# multiplexer-ic.net
KiCad netlist of a schematic drawn in Altium Designer
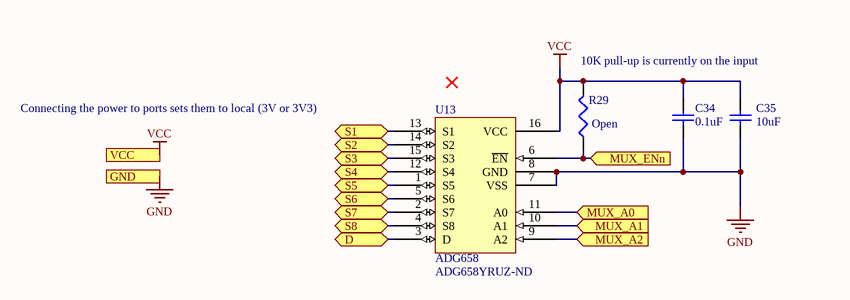
[diagram p0: multiplexer-ic.SchDoc]

(export (version "E")
  (design (tool "Eeschema 10.0.6"))
  (components
    (comp (ref "C34")
      (value "0.1uF")
      (footprint "0402")
      (description "Capacitor (Semiconductor SIM Model)")
      (fields (field (name "PUBLISHER") "Altium Limited"))
      (libsource (lib "Miscellaneous Devices") (part "Cap Semi"))
    )
    (comp (ref "C35")
      (value "10uF")
      (footprint "1608[0603]")
      (description "Capacitor (Semiconductor SIM Model)")
      (fields (field (name "PUBLISHER") "Altium Limited"))
      (libsource (lib "Miscellaneous Devices") (part "Cap Semi"))
    )
    (comp (ref "R29")
      (value "Open")
      (footprint "0402")
      (description "Resistor")
      (fields (field (name "Comment") "Optional 10K") (field (name "PUBLISHER") "Altium Limited"))
      (libsource (lib "Miscellaneous Devices") (part "Res3"))
    )
    (comp (ref "U13")
      (value "ADG658")
      (footprint "SSOP16_N")
      (description "Eight channel analog multiplexer.")
      (fields (field (name "SUPPLIER PART NUMBER 1") "ADG658YRUZ-ND"))
      (libsource (lib "PAY") (part "ADG658"))
    )
  )
  (nets
    (net (code "1") (name "/D") (class "Default")
      (node (ref "U13") (pin "3") (pinfunction "D_3") (pintype "bidirectional"))
    )
    (net (code "2") (name "/MUX_A0") (class "Default")
      (node (ref "U13") (pin "11") (pinfunction "A0_11") (pintype "input"))
    )
    (net (code "3") (name "/MUX_A1") (class "Default")
      (node (ref "U13") (pin "10") (pinfunction "A1_10") (pintype "input"))
    )
    (net (code "4") (name "/MUX_A2") (class "Default")
      (node (ref "U13") (pin "9") (pinfunction "A2_9") (pintype "input"))
    )
    (net (code "5") (name "/MUX_ENn") (class "Default")
      (node (ref "R29") (pin "1") (pinfunction "1_1") (pintype "passive"))
      (node (ref "U13") (pin "6") (pinfunction "~{EN}_6") (pintype "input"))
    )
    (net (code "6") (name "/S1") (class "Default")
      (node (ref "U13") (pin "13") (pinfunction "S1_13") (pintype "bidirectional"))
    )
    (net (code "7") (name "/S2") (class "Default")
      (node (ref "U13") (pin "14") (pinfunction "S2_14") (pintype "bidirectional"))
    )
    (net (code "8") (name "/S3") (class "Default")
      (node (ref "U13") (pin "15") (pinfunction "S3_15") (pintype "bidirectional"))
    )
    (net (code "9") (name "/S4") (class "Default")
      (node (ref "U13") (pin "12") (pinfunction "S4_12") (pintype "bidirectional"))
    )
    (net (code "10") (name "/S5") (class "Default")
      (node (ref "U13") (pin "1") (pinfunction "S5_1") (pintype "bidirectional"))
    )
    (net (code "11") (name "/S6") (class "Default")
      (node (ref "U13") (pin "5") (pinfunction "S6_5") (pintype "bidirectional"))
    )
    (net (code "12") (name "/S7") (class "Default")
      (node (ref "U13") (pin "2") (pinfunction "S7_2") (pintype "bidirectional"))
    )
    (net (code "13") (name "/S8") (class "Default")
      (node (ref "U13") (pin "4") (pinfunction "S8_4") (pintype "bidirectional"))
    )
    (net (code "14") (name "GND") (class "Default")
      (node (ref "C34") (pin "1") (pinfunction "1_1") (pintype "passive"))
      (node (ref "C35") (pin "1") (pinfunction "1_1") (pintype "passive"))
      (node (ref "U13") (pin "7") (pinfunction "VSS_7") (pintype "power_in"))
      (node (ref "U13") (pin "8") (pinfunction "GND_8") (pintype "power_in"))
    )
    (net (code "15") (name "VCC") (class "Default")
      (node (ref "C34") (pin "2") (pinfunction "2_2") (pintype "passive"))
      (node (ref "C35") (pin "2") (pinfunction "2_2") (pintype "passive"))
      (node (ref "R29") (pin "2") (pinfunction "2_2") (pintype "passive"))
      (node (ref "U13") (pin "16") (pinfunction "VCC_16") (pintype "power_in"))
    )
  )
)
